# TUSB8041-Q1-4port_Hub.net
KiCad netlist of a schematic drawn in Altium Designer
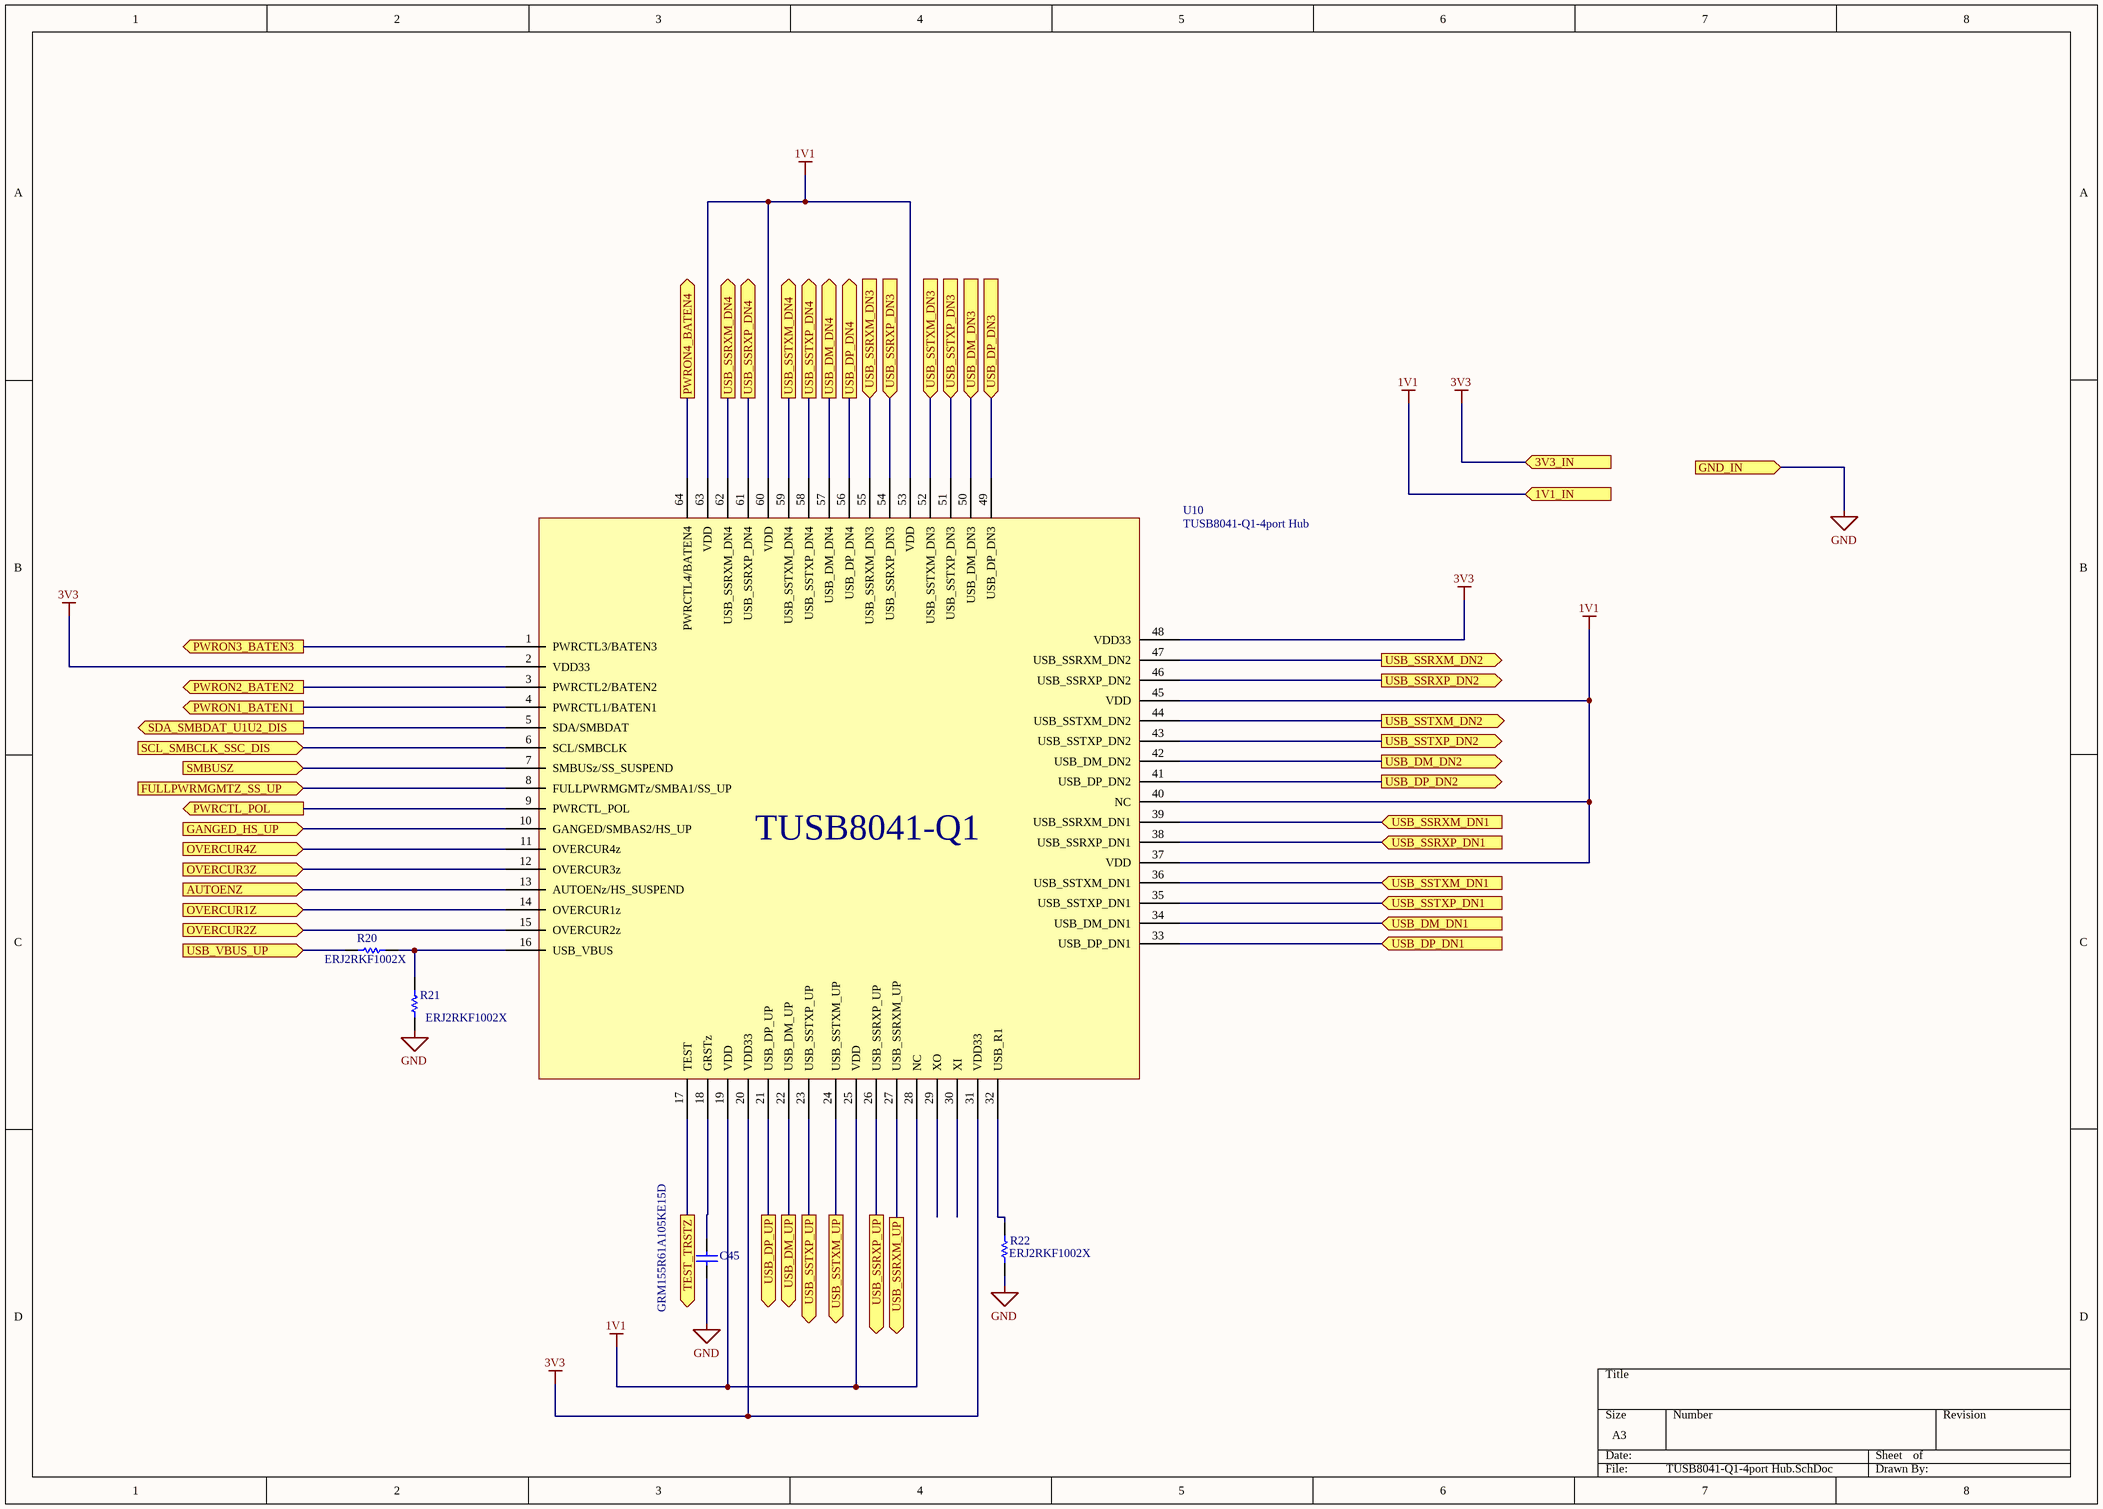
[diagram p0: TUSB8041-Q1-4port Hub.SchDoc]

(export (version "E")
  (design (tool "Eeschema 10.0.6"))
  (components
    (comp (ref "C45")
      (value "GRM155R61A105KE15D")
      (footprint "CAPC1005X55X25NL05T10")
      (fields (field (name "MANUFACTURER") "Murata"))
      (libsource (lib "Altium Content Vault") (part "CAP"))
    )
    (comp (ref "R20")
      (value "ERJ2RKF1002X")
      (footprint "RESC1005X40X25LL05T05")
      (description "Chip Resistor, 10 KOhm, +/- 1%, 0.1 W, -55 to 155 degC, 0402 (1005 Metric), RoHS, Tape and Reel")
      (fields (field (name "TOLERANCE") "1%") (field (name "MANUFACTURER") "Panasonic"))
      (libsource (lib "Altium Content Vault") (part "RES-2"))
    )
    (comp (ref "R21")
      (value "ERJ2RKF1002X")
      (footprint "RESC1005X40X25LL05T05")
      (description "Chip Resistor, 10 KOhm, +/- 1%, 0.1 W, -55 to 155 degC, 0402 (1005 Metric), RoHS, Tape and Reel")
      (fields (field (name "TOLERANCE") "1%") (field (name "MANUFACTURER") "Panasonic"))
      (libsource (lib "Altium Content Vault") (part "RES-2"))
    )
    (comp (ref "R22")
      (value "ERJ2RKF1002X")
      (footprint "RESC1005X40X25LL05T05")
      (description "Chip Resistor, 10 KOhm, +/- 1%, 0.1 W, -55 to 155 degC, 0402 (1005 Metric), RoHS, Tape and Reel")
      (fields (field (name "TOLERANCE") "1%") (field (name "MANUFACTURER") "Panasonic"))
      (libsource (lib "Altium Content Vault") (part "RES-2"))
    )
    (comp (ref "U10")
      (value "TUSB8041-Q1-4port Hub")
      (footprint "TSQFP50P1200X1200X120-64N")
      (libsource (lib "PlumPot_Library") (part "TUSB8041-Q1-4port Hub"))
    )
  )
  (nets
    (net (code "1") (name "/AUTOENZ") (class "Default")
      (node (ref "U10") (pin "13") (pinfunction "AUTOENz/HS_SUSPEND_13") (pintype "passive"))
    )
    (net (code "2") (name "/FULLPWRMGMTZ_SS_UP") (class "Default")
      (node (ref "U10") (pin "8") (pinfunction "FULLPWRMGMTz/SMBA1/SS_UP_8") (pintype "passive"))
    )
    (net (code "3") (name "/GANGED_HS_UP") (class "Default")
      (node (ref "U10") (pin "10") (pinfunction "GANGED/SMBAS2/HS_UP_10") (pintype "passive"))
    )
    (net (code "4") (name "/OVERCUR1Z") (class "Default")
      (node (ref "U10") (pin "14") (pinfunction "OVERCUR1z_14") (pintype "passive"))
    )
    (net (code "5") (name "/OVERCUR2Z") (class "Default")
      (node (ref "U10") (pin "15") (pinfunction "OVERCUR2z_15") (pintype "passive"))
    )
    (net (code "6") (name "/OVERCUR3Z") (class "Default")
      (node (ref "U10") (pin "12") (pinfunction "OVERCUR3z_12") (pintype "passive"))
    )
    (net (code "7") (name "/OVERCUR4Z") (class "Default")
      (node (ref "U10") (pin "11") (pinfunction "OVERCUR4z_11") (pintype "passive"))
    )
    (net (code "8") (name "/PWRCTL_POL") (class "Default")
      (node (ref "U10") (pin "9") (pinfunction "PWRCTL_POL_9") (pintype "passive"))
    )
    (net (code "9") (name "/PWRON1_BATEN1") (class "Default")
      (node (ref "U10") (pin "4") (pinfunction "PWRCTL1/BATEN1_4") (pintype "passive"))
    )
    (net (code "10") (name "/PWRON2_BATEN2") (class "Default")
      (node (ref "U10") (pin "3") (pinfunction "PWRCTL2/BATEN2_3") (pintype "passive"))
    )
    (net (code "11") (name "/PWRON3_BATEN3") (class "Default")
      (node (ref "U10") (pin "1") (pinfunction "PWRCTL3/BATEN3_1") (pintype "passive"))
    )
    (net (code "12") (name "/PWRON4_BATEN4") (class "Default")
      (node (ref "U10") (pin "64") (pinfunction "PWRCTL4/BATEN4_64") (pintype "passive"))
    )
    (net (code "13") (name "/SCL_SMBCLK_SSC_DIS") (class "Default")
      (node (ref "U10") (pin "6") (pinfunction "SCL/SMBCLK_6") (pintype "passive"))
    )
    (net (code "14") (name "/SDA_SMBDAT_U1U2_DIS") (class "Default")
      (node (ref "U10") (pin "5") (pinfunction "SDA/SMBDAT_5") (pintype "passive"))
    )
    (net (code "15") (name "/SMBUSZ") (class "Default")
      (node (ref "U10") (pin "7") (pinfunction "SMBUSz/SS_SUSPEND_7") (pintype "passive"))
    )
    (net (code "16") (name "/TEST_TRSTZ") (class "Default")
      (node (ref "U10") (pin "17") (pinfunction "TEST_17") (pintype "passive"))
    )
    (net (code "17") (name "/USB_DM_DN1") (class "Default")
      (node (ref "U10") (pin "34") (pinfunction "USB_DM_DN1_34") (pintype "passive"))
    )
    (net (code "18") (name "/USB_DM_DN2") (class "Default")
      (node (ref "U10") (pin "42") (pinfunction "USB_DM_DN2_42") (pintype "passive"))
    )
    (net (code "19") (name "/USB_DM_DN3") (class "Default")
      (node (ref "U10") (pin "50") (pinfunction "USB_DM_DN3_50") (pintype "passive"))
    )
    (net (code "20") (name "/USB_DM_DN4") (class "Default")
      (node (ref "U10") (pin "57") (pinfunction "USB_DM_DN4_57") (pintype "passive"))
    )
    (net (code "21") (name "/USB_DM_UP") (class "Default")
      (node (ref "U10") (pin "22") (pinfunction "USB_DM_UP_22") (pintype "passive"))
    )
    (net (code "22") (name "/USB_DP_DN1") (class "Default")
      (node (ref "U10") (pin "33") (pinfunction "USB_DP_DN1_33") (pintype "passive"))
    )
    (net (code "23") (name "/USB_DP_DN2") (class "Default")
      (node (ref "U10") (pin "41") (pinfunction "USB_DP_DN2_41") (pintype "passive"))
    )
    (net (code "24") (name "/USB_DP_DN3") (class "Default")
      (node (ref "U10") (pin "49") (pinfunction "USB_DP_DN3_49") (pintype "passive"))
    )
    (net (code "25") (name "/USB_DP_DN4") (class "Default")
      (node (ref "U10") (pin "56") (pinfunction "USB_DP_DN4_56") (pintype "passive"))
    )
    (net (code "26") (name "/USB_DP_UP") (class "Default")
      (node (ref "U10") (pin "21") (pinfunction "USB_DP_UP_21") (pintype "passive"))
    )
    (net (code "27") (name "/USB_SSRXM_DN1") (class "Default")
      (node (ref "U10") (pin "39") (pinfunction "USB_SSRXM_DN1_39") (pintype "passive"))
    )
    (net (code "28") (name "/USB_SSRXM_DN2") (class "Default")
      (node (ref "U10") (pin "47") (pinfunction "USB_SSRXM_DN2_47") (pintype "passive"))
    )
    (net (code "29") (name "/USB_SSRXM_DN3") (class "Default")
      (node (ref "U10") (pin "55") (pinfunction "USB_SSRXM_DN3_55") (pintype "passive"))
    )
    (net (code "30") (name "/USB_SSRXM_DN4") (class "Default")
      (node (ref "U10") (pin "62") (pinfunction "USB_SSRXM_DN4_62") (pintype "passive"))
    )
    (net (code "31") (name "/USB_SSRXM_UP") (class "Default")
      (node (ref "U10") (pin "27") (pinfunction "USB_SSRXM_UP_27") (pintype "passive"))
    )
    (net (code "32") (name "/USB_SSRXP_DN1") (class "Default")
      (node (ref "U10") (pin "38") (pinfunction "USB_SSRXP_DN1_38") (pintype "passive"))
    )
    (net (code "33") (name "/USB_SSRXP_DN2") (class "Default")
      (node (ref "U10") (pin "46") (pinfunction "USB_SSRXP_DN2_46") (pintype "passive"))
    )
    (net (code "34") (name "/USB_SSRXP_DN3") (class "Default")
      (node (ref "U10") (pin "54") (pinfunction "USB_SSRXP_DN3_54") (pintype "passive"))
    )
    (net (code "35") (name "/USB_SSRXP_DN4") (class "Default")
      (node (ref "U10") (pin "61") (pinfunction "USB_SSRXP_DN4_61") (pintype "passive"))
    )
    (net (code "36") (name "/USB_SSRXP_UP") (class "Default")
      (node (ref "U10") (pin "26") (pinfunction "USB_SSRXP_UP_26") (pintype "passive"))
    )
    (net (code "37") (name "/USB_SSTXM_DN1") (class "Default")
      (node (ref "U10") (pin "36") (pinfunction "USB_SSTXM_DN1_36") (pintype "passive"))
    )
    (net (code "38") (name "/USB_SSTXM_DN2") (class "Default")
      (node (ref "U10") (pin "44") (pinfunction "USB_SSTXM_DN2_44") (pintype "passive"))
    )
    (net (code "39") (name "/USB_SSTXM_DN3") (class "Default")
      (node (ref "U10") (pin "52") (pinfunction "USB_SSTXM_DN3_52") (pintype "passive"))
    )
    (net (code "40") (name "/USB_SSTXM_DN4") (class "Default")
      (node (ref "U10") (pin "59") (pinfunction "USB_SSTXM_DN4_59") (pintype "passive"))
    )
    (net (code "41") (name "/USB_SSTXM_UP") (class "Default")
      (node (ref "U10") (pin "24") (pinfunction "USB_SSTXM_UP_24") (pintype "passive"))
    )
    (net (code "42") (name "/USB_SSTXP_DN1") (class "Default")
      (node (ref "U10") (pin "35") (pinfunction "USB_SSTXP_DN1_35") (pintype "passive"))
    )
    (net (code "43") (name "/USB_SSTXP_DN2") (class "Default")
      (node (ref "U10") (pin "43") (pinfunction "USB_SSTXP_DN2_43") (pintype "passive"))
    )
    (net (code "44") (name "/USB_SSTXP_DN3") (class "Default")
      (node (ref "U10") (pin "51") (pinfunction "USB_SSTXP_DN3_51") (pintype "passive"))
    )
    (net (code "45") (name "/USB_SSTXP_DN4") (class "Default")
      (node (ref "U10") (pin "58") (pinfunction "USB_SSTXP_DN4_58") (pintype "passive"))
    )
    (net (code "46") (name "/USB_SSTXP_UP") (class "Default")
      (node (ref "U10") (pin "23") (pinfunction "USB_SSTXP_UP_23") (pintype "passive"))
    )
    (net (code "47") (name "/USB_VBUS_UP") (class "Default")
      (node (ref "R20") (pin "2") (pinfunction "2_2") (pintype "passive"))
    )
    (net (code "48") (name "1V1") (class "Default")
      (node (ref "U10") (pin "19") (pinfunction "VDD_19") (pintype "passive"))
      (node (ref "U10") (pin "25") (pinfunction "VDD_25") (pintype "passive"))
      (node (ref "U10") (pin "28") (pinfunction "NC_28") (pintype "passive"))
      (node (ref "U10") (pin "37") (pinfunction "VDD_37") (pintype "passive"))
      (node (ref "U10") (pin "40") (pinfunction "NC_40") (pintype "passive"))
      (node (ref "U10") (pin "45") (pinfunction "VDD_45") (pintype "passive"))
      (node (ref "U10") (pin "53") (pinfunction "VDD_53") (pintype "passive"))
      (node (ref "U10") (pin "60") (pinfunction "VDD_60") (pintype "passive"))
      (node (ref "U10") (pin "63") (pinfunction "VDD_63") (pintype "passive"))
    )
    (net (code "49") (name "3V3") (class "Default")
      (node (ref "U10") (pin "2") (pinfunction "VDD33_2") (pintype "passive"))
      (node (ref "U10") (pin "20") (pinfunction "VDD33_20") (pintype "passive"))
      (node (ref "U10") (pin "31") (pinfunction "VDD33_31") (pintype "passive"))
      (node (ref "U10") (pin "48") (pinfunction "VDD33_48") (pintype "passive"))
    )
    (net (code "50") (name "GND") (class "Default")
      (node (ref "C45") (pin "1") (pinfunction "1_1") (pintype "passive"))
      (node (ref "R21") (pin "1") (pinfunction "1_1") (pintype "passive"))
      (node (ref "R22") (pin "1") (pinfunction "1_1") (pintype "passive"))
    )
    (net (code "51") (name "Net-(U10-GRSTz)") (class "Default")
      (node (ref "C45") (pin "2") (pinfunction "2_2") (pintype "passive"))
      (node (ref "U10") (pin "18") (pinfunction "GRSTz_18") (pintype "passive"))
    )
    (net (code "52") (name "Net-(U10-USB_R1)") (class "Default")
      (node (ref "R22") (pin "2") (pinfunction "2_2") (pintype "passive"))
      (node (ref "U10") (pin "32") (pinfunction "USB_R1_32") (pintype "passive"))
    )
    (net (code "53") (name "Net-(U10-USB_VBUS)") (class "Default")
      (node (ref "R20") (pin "1") (pinfunction "1_1") (pintype "passive"))
      (node (ref "R21") (pin "2") (pinfunction "2_2") (pintype "passive"))
      (node (ref "U10") (pin "16") (pinfunction "USB_VBUS_16") (pintype "passive"))
    )
    (net (code "54") (name "unconnected-(U10-XI-Pad30)") (class "Default")
      (node (ref "U10") (pin "30") (pinfunction "XI_30") (pintype "passive"))
    )
    (net (code "55") (name "unconnected-(U10-XO-Pad29)") (class "Default")
      (node (ref "U10") (pin "29") (pinfunction "XO_29") (pintype "passive"))
    )
  )
)
